# multi-pcb-switches.net
KiCad netlist of a schematic drawn in EAGLE
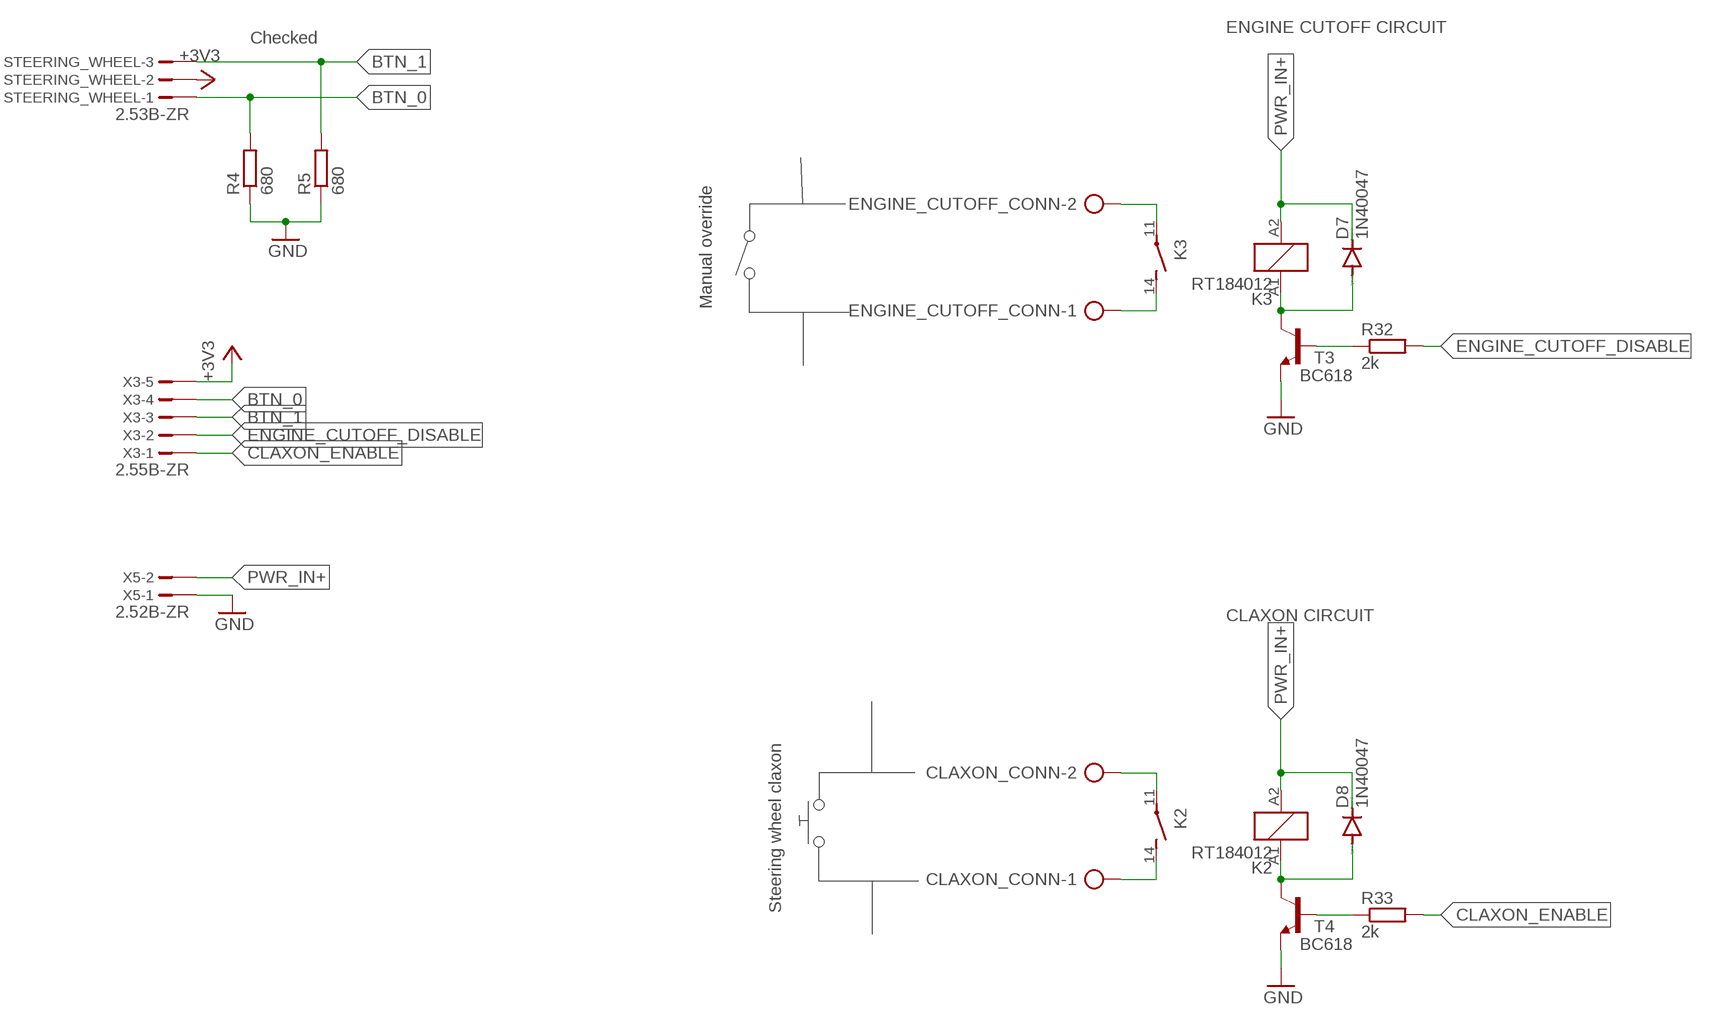
[diagram p0: schematic, sheet 1]

(export (version "E")
  (design (tool "Eeschema 10.0.6"))
  (components
    (comp (ref "CLAXON_CONN")
      (value "AK300/2")
      (footprint "eagle-import:AK300_2")
      (libsource (lib "eagle-import") (part "AK300/2"))
    )
    (comp (ref "D7")
      (value "1N40047")
      (footprint "eagle-import:DO41-7.6")
      (libsource (lib "eagle-import") (part "1N40047"))
    )
    (comp (ref "D8")
      (value "1N40047")
      (footprint "eagle-import:DO41-7.6")
      (libsource (lib "eagle-import") (part "1N40047"))
    )
    (comp (ref "ENGINE_CUTOFF_CONN")
      (value "AK300/2")
      (footprint "eagle-import:AK300_2")
      (libsource (lib "eagle-import") (part "AK300/2"))
    )
    (comp (ref "K2")
      (value "RT184012")
      (footprint "eagle-import:RT-N_O12A3.5")
      (fields (field (name "MF") "TYCO ELECTRONICS"))
      (libsource (lib "eagle-import") (part "RT?184012"))
    )
    (comp (ref "K3")
      (value "RT184012")
      (footprint "eagle-import:RT-N_O12A3.5")
      (fields (field (name "MF") "TYCO ELECTRONICS"))
      (libsource (lib "eagle-import") (part "RT?184012"))
    )
    (comp (ref "R4")
      (value "680")
      (footprint "eagle-import:0207_7")
      (libsource (lib "eagle-import") (part "R-EU_0207/7"))
    )
    (comp (ref "R5")
      (value "680")
      (footprint "eagle-import:0207_7")
      (libsource (lib "eagle-import") (part "R-EU_0207/7"))
    )
    (comp (ref "R32")
      (value "2k")
      (footprint "eagle-import:0207_7")
      (libsource (lib "eagle-import") (part "R-EU_0207/7"))
    )
    (comp (ref "R33")
      (value "2k")
      (footprint "eagle-import:0207_7")
      (libsource (lib "eagle-import") (part "R-EU_0207/7"))
    )
    (comp (ref "STEERING_WHEEL")
      (value "2.53B-ZR")
      (footprint "eagle-import:B3B-ZR2.5")
      (libsource (lib "eagle-import") (part "?3B-ZR2.5"))
    )
    (comp (ref "T3")
      (value "BC618")
      (footprint "eagle-import:TO92-EBC")
      (libsource (lib "eagle-import") (part "BC618"))
    )
    (comp (ref "T4")
      (value "BC618")
      (footprint "eagle-import:TO92-EBC")
      (libsource (lib "eagle-import") (part "BC618"))
    )
    (comp (ref "X3")
      (value "2.55B-ZR")
      (footprint "eagle-import:B5B-ZR2.5")
      (libsource (lib "eagle-import") (part "?5B-ZR2.5"))
    )
    (comp (ref "X5")
      (value "2.52B-ZR")
      (footprint "eagle-import:B2B-ZR2.5")
      (libsource (lib "eagle-import") (part "?2B-ZR2.5"))
    )
  )
  (nets
    (net (code "1") (name "+3V3") (class "Default")
      (node (ref "STEERING_WHEEL") (pin "2") (pinfunction "1_2") (pintype "passive"))
      (node (ref "X3") (pin "5") (pinfunction "1_5") (pintype "passive"))
    )
    (net (code "2") (name "BTN_0") (class "Default")
      (node (ref "R4") (pin "2") (pinfunction "2_2") (pintype "passive"))
      (node (ref "STEERING_WHEEL") (pin "1") (pinfunction "1_1") (pintype "passive"))
      (node (ref "X3") (pin "4") (pinfunction "1_4") (pintype "passive"))
    )
    (net (code "3") (name "BTN_1") (class "Default")
      (node (ref "R5") (pin "2") (pinfunction "2_2") (pintype "passive"))
      (node (ref "STEERING_WHEEL") (pin "3") (pinfunction "1_3") (pintype "passive"))
      (node (ref "X3") (pin "3") (pinfunction "1_3") (pintype "passive"))
    )
    (net (code "4") (name "CLAXON_ENABLE") (class "Default")
      (node (ref "R33") (pin "2") (pinfunction "2_2") (pintype "passive"))
      (node (ref "X3") (pin "1") (pinfunction "1_1") (pintype "passive"))
    )
    (net (code "5") (name "ENGINE_CUTOFF_DISABLE") (class "Default")
      (node (ref "R32") (pin "2") (pinfunction "2_2") (pintype "passive"))
      (node (ref "X3") (pin "2") (pinfunction "1_2") (pintype "passive"))
    )
    (net (code "6") (name "GND") (class "Default")
      (node (ref "R4") (pin "1") (pinfunction "1_1") (pintype "passive"))
      (node (ref "R5") (pin "1") (pinfunction "1_1") (pintype "passive"))
      (node (ref "T3") (pin "E") (pinfunction "E_E") (pintype "passive"))
      (node (ref "T4") (pin "E") (pinfunction "E_E") (pintype "passive"))
      (node (ref "X5") (pin "1") (pinfunction "1_1") (pintype "passive"))
    )
    (net (code "7") (name "Net-(CLAXON_CONNA-KL)") (class "Default")
      (node (ref "CLAXON_CONN") (pin "1") (pinfunction "KL_1") (pintype "passive"))
      (node (ref "K2") (pin "14") (pinfunction "S_14") (pintype "passive"))
    )
    (net (code "8") (name "Net-(CLAXON_CONNB-KL)") (class "Default")
      (node (ref "CLAXON_CONN") (pin "2") (pinfunction "KL_2") (pintype "passive"))
      (node (ref "K2") (pin "11") (pinfunction "P_11") (pintype "passive"))
    )
    (net (code "9") (name "Net-(ENGINE_CUTOFF_CONNA-KL)") (class "Default")
      (node (ref "ENGINE_CUTOFF_CONN") (pin "1") (pinfunction "KL_1") (pintype "passive"))
      (node (ref "K3") (pin "14") (pinfunction "S_14") (pintype "passive"))
    )
    (net (code "10") (name "Net-(ENGINE_CUTOFF_CONNB-KL)") (class "Default")
      (node (ref "ENGINE_CUTOFF_CONN") (pin "2") (pinfunction "KL_2") (pintype "passive"))
      (node (ref "K3") (pin "11") (pinfunction "P_11") (pintype "passive"))
    )
    (net (code "11") (name "Net-(K2A-1)") (class "Default")
      (node (ref "D8") (pin "A") (pinfunction "A_A") (pintype "passive"))
      (node (ref "K2") (pin "A1") (pinfunction "1_A1") (pintype "passive"))
      (node (ref "T4") (pin "C") (pinfunction "C_C") (pintype "passive"))
    )
    (net (code "12") (name "Net-(K3A-1)") (class "Default")
      (node (ref "D7") (pin "A") (pinfunction "A_A") (pintype "passive"))
      (node (ref "K3") (pin "A1") (pinfunction "1_A1") (pintype "passive"))
      (node (ref "T3") (pin "C") (pinfunction "C_C") (pintype "passive"))
    )
    (net (code "13") (name "Net-(R32-Pad1)") (class "Default")
      (node (ref "R32") (pin "1") (pinfunction "1_1") (pintype "passive"))
      (node (ref "T3") (pin "B") (pinfunction "B_B") (pintype "passive"))
    )
    (net (code "14") (name "Net-(R33-Pad1)") (class "Default")
      (node (ref "R33") (pin "1") (pinfunction "1_1") (pintype "passive"))
      (node (ref "T4") (pin "B") (pinfunction "B_B") (pintype "passive"))
    )
    (net (code "15") (name "PWR_IN+") (class "Default")
      (node (ref "D7") (pin "C") (pinfunction "C_C") (pintype "passive"))
      (node (ref "D8") (pin "C") (pinfunction "C_C") (pintype "passive"))
      (node (ref "K2") (pin "A2") (pinfunction "2_A2") (pintype "passive"))
      (node (ref "K3") (pin "A2") (pinfunction "2_A2") (pintype "passive"))
      (node (ref "X5") (pin "2") (pinfunction "1_2") (pintype "passive"))
    )
  )
)
